# acl-adapter.net
KiCad netlist of a schematic drawn in EAGLE
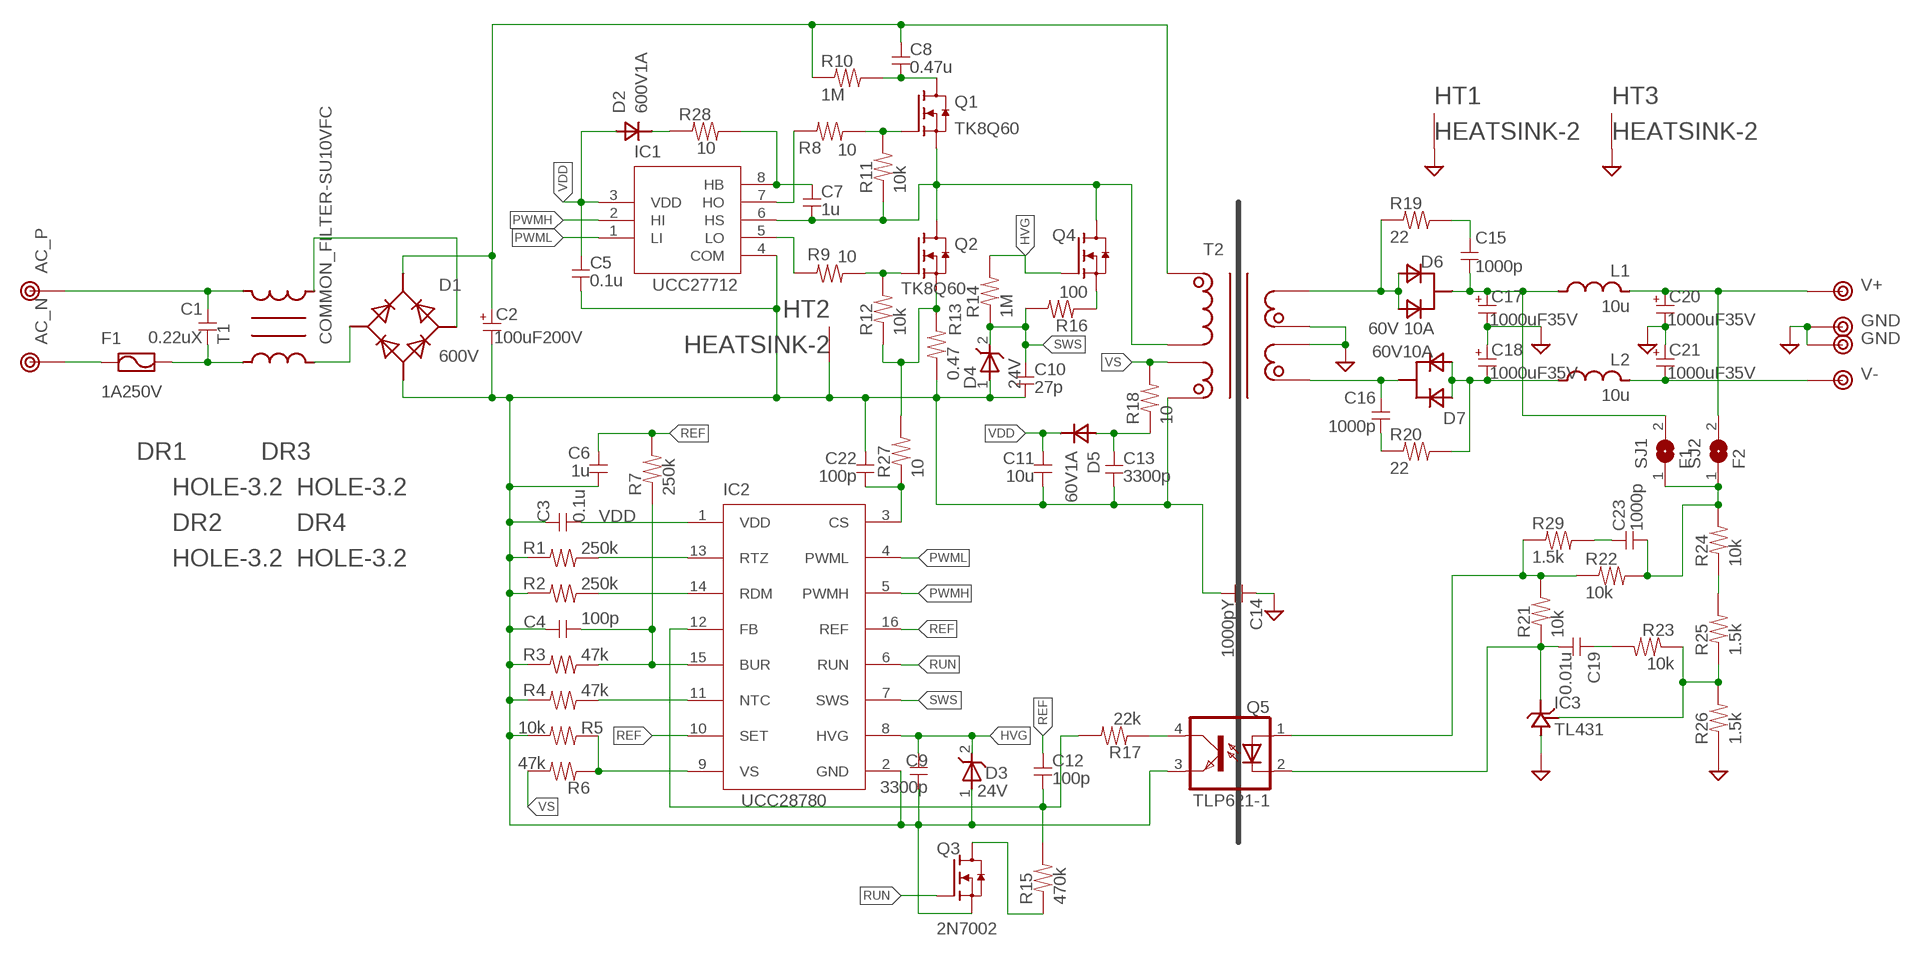
[diagram p0: schematic, sheet 1]

(export (version "E")
  (design (tool "Eeschema 10.0.6"))
  (components
    (comp (ref "C1")
      (value "0.22uX")
      (footprint "eagle-import:X-CAPACITER")
      (libsource (lib "eagle-import") (part "C-X"))
    )
    (comp (ref "C2")
      (value "100uF200V")
      (footprint "eagle-import:E5-10,5A2")
      (libsource (lib "eagle-import") (part "CPOLE5-10.5A2"))
    )
    (comp (ref "C3")
      (value "0.1u")
      (footprint "eagle-import:1608")
      (libsource (lib "eagle-import") (part "C-1608"))
    )
    (comp (ref "C4")
      (value "100p")
      (footprint "eagle-import:1608")
      (libsource (lib "eagle-import") (part "C-1608"))
    )
    (comp (ref "C5")
      (value "0.1u")
      (footprint "eagle-import:1608")
      (libsource (lib "eagle-import") (part "C-1608"))
    )
    (comp (ref "C6")
      (value "1u")
      (footprint "eagle-import:1608")
      (libsource (lib "eagle-import") (part "C-1608"))
    )
    (comp (ref "C7")
      (value "1u")
      (footprint "eagle-import:1608")
      (libsource (lib "eagle-import") (part "C-1608"))
    )
    (comp (ref "C8")
      (value "0.47u")
      (footprint "eagle-import:C075")
      (libsource (lib "eagle-import") (part "C-7.5"))
    )
    (comp (ref "C9")
      (value "3300p")
      (footprint "eagle-import:1608")
      (libsource (lib "eagle-import") (part "C-1608"))
    )
    (comp (ref "C10")
      (value "27p")
      (footprint "eagle-import:1608")
      (libsource (lib "eagle-import") (part "C-1608"))
    )
    (comp (ref "C11")
      (value "10u")
      (footprint "eagle-import:2012")
      (libsource (lib "eagle-import") (part "C-2012"))
    )
    (comp (ref "C12")
      (value "100p")
      (footprint "eagle-import:1608")
      (libsource (lib "eagle-import") (part "C-1608"))
    )
    (comp (ref "C13")
      (value "3300p")
      (footprint "eagle-import:1608")
      (libsource (lib "eagle-import") (part "C-1608"))
    )
    (comp (ref "C14")
      (value "1000pY")
      (footprint "eagle-import:Y-CAPACITER")
      (libsource (lib "eagle-import") (part "C-Y"))
    )
    (comp (ref "C15")
      (value "1000p")
      (footprint "eagle-import:1608")
      (libsource (lib "eagle-import") (part "C-1608"))
    )
    (comp (ref "C16")
      (value "1000p")
      (footprint "eagle-import:1608")
      (libsource (lib "eagle-import") (part "C-1608"))
    )
    (comp (ref "C17")
      (value "1000uF35V")
      (footprint "eagle-import:E5-10")
      (libsource (lib "eagle-import") (part "CPOLE5-10"))
    )
    (comp (ref "C18")
      (value "1000uF35V")
      (footprint "eagle-import:E5-10")
      (libsource (lib "eagle-import") (part "CPOLE5-10"))
    )
    (comp (ref "C19")
      (value "0.01u")
      (footprint "eagle-import:1608")
      (libsource (lib "eagle-import") (part "C-1608"))
    )
    (comp (ref "C20")
      (value "1000uF35V")
      (footprint "eagle-import:E5-10")
      (libsource (lib "eagle-import") (part "CPOLE5-10"))
    )
    (comp (ref "C21")
      (value "1000uF35V")
      (footprint "eagle-import:E5-10")
      (libsource (lib "eagle-import") (part "CPOLE5-10"))
    )
    (comp (ref "C22")
      (value "100p")
      (footprint "eagle-import:1608")
      (libsource (lib "eagle-import") (part "C-1608"))
    )
    (comp (ref "C23")
      (value "1000p")
      (footprint "eagle-import:1608")
      (libsource (lib "eagle-import") (part "C-1608"))
    )
    (comp (ref "D1")
      (value "600V")
      (footprint "eagle-import:GBU8A")
      (libsource (lib "eagle-import") (part "DIODE4-GBU8A"))
    )
    (comp (ref "D2")
      (value "600V1A")
      (footprint "eagle-import:D0204_7")
      (libsource (lib "eagle-import") (part "DIODE-7"))
    )
    (comp (ref "D3")
      (value "24V")
      (footprint "eagle-import:SOD123")
      (libsource (lib "eagle-import") (part "ZENER-SMD"))
    )
    (comp (ref "D4")
      (value "24V")
      (footprint "eagle-import:SOD123")
      (libsource (lib "eagle-import") (part "ZENER-SMD"))
    )
    (comp (ref "D5")
      (value "60V1A")
      (footprint "eagle-import:D0204_7")
      (libsource (lib "eagle-import") (part "DIODE-7"))
    )
    (comp (ref "D6")
      (value "60V 10A")
      (footprint "eagle-import:TO-220")
      (libsource (lib "eagle-import") (part "DIODE2"))
    )
    (comp (ref "D7")
      (value "60V10A")
      (footprint "eagle-import:TO-220")
      (libsource (lib "eagle-import") (part "DIODE2"))
    )
    (comp (ref "DR1")
      (value "HOLE-3.2")
      (footprint "eagle-import:HOLE_3.2")
      (libsource (lib "eagle-import") (part "HOLE-3.2"))
    )
    (comp (ref "DR2")
      (value "HOLE-3.2")
      (footprint "eagle-import:HOLE_3.2")
      (libsource (lib "eagle-import") (part "HOLE-3.2"))
    )
    (comp (ref "DR3")
      (value "HOLE-3.2")
      (footprint "eagle-import:HOLE_3.2")
      (libsource (lib "eagle-import") (part "HOLE-3.2"))
    )
    (comp (ref "DR4")
      (value "HOLE-3.2")
      (footprint "eagle-import:HOLE_3.2")
      (libsource (lib "eagle-import") (part "HOLE-3.2"))
    )
    (comp (ref "F1")
      (value "1A250V")
      (footprint "eagle-import:FUSE-5")
      (libsource (lib "eagle-import") (part "FUSE-5"))
    )
    (comp (ref "HT1")
      (value "HEATSINK-2")
      (footprint "eagle-import:HEATSINK2")
      (libsource (lib "eagle-import") (part "HEATSINK-2"))
    )
    (comp (ref "HT2")
      (value "HEATSINK-2")
      (footprint "eagle-import:HEATSINK2")
      (libsource (lib "eagle-import") (part "HEATSINK-2"))
    )
    (comp (ref "HT3")
      (value "HEATSINK-2")
      (footprint "eagle-import:HEATSINK2")
      (libsource (lib "eagle-import") (part "HEATSINK-2"))
    )
    (comp (ref "IC1")
      (value "UCC27712")
      (footprint "eagle-import:SOP8")
      (libsource (lib "eagle-import") (part "UCC27712"))
    )
    (comp (ref "IC2")
      (value "UCC28780")
      (footprint "eagle-import:SO16")
      (libsource (lib "eagle-import") (part "UCC28780"))
    )
    (comp (ref "IC3")
      (value "TL431")
      (footprint "eagle-import:TO-92")
      (libsource (lib "eagle-import") (part "TL431"))
    )
    (comp (ref "L1")
      (value "10u")
      (footprint "eagle-import:L5-7,5")
      (libsource (lib "eagle-import") (part "L-5"))
    )
    (comp (ref "L2")
      (value "10u")
      (footprint "eagle-import:L5-7,5")
      (libsource (lib "eagle-import") (part "L-5"))
    )
    (comp (ref "Q1")
      (value "TK8Q60")
      (footprint "eagle-import:TO-220")
      (libsource (lib "eagle-import") (part "NMOS"))
    )
    (comp (ref "Q2")
      (value "TK8Q60")
      (footprint "eagle-import:TO-220")
      (libsource (lib "eagle-import") (part "NMOS"))
    )
    (comp (ref "Q3")
      (value "2N7002")
      (footprint "eagle-import:SC59")
      (libsource (lib "eagle-import") (part "NMOS-SMD"))
    )
    (comp (ref "Q4")
      (value "NMOS-SMD")
      (footprint "eagle-import:SC59")
      (libsource (lib "eagle-import") (part "NMOS-SMD"))
    )
    (comp (ref "Q5")
      (value "TLP621-1")
      (footprint "eagle-import:DIL04")
      (libsource (lib "eagle-import") (part "TLP621-1"))
    )
    (comp (ref "R1")
      (value "250k")
      (footprint "eagle-import:1608")
      (libsource (lib "eagle-import") (part "R-1608"))
    )
    (comp (ref "R2")
      (value "250k")
      (footprint "eagle-import:1608")
      (libsource (lib "eagle-import") (part "R-1608"))
    )
    (comp (ref "R3")
      (value "47k")
      (footprint "eagle-import:1608")
      (libsource (lib "eagle-import") (part "R-1608"))
    )
    (comp (ref "R4")
      (value "47k")
      (footprint "eagle-import:1608")
      (libsource (lib "eagle-import") (part "R-1608"))
    )
    (comp (ref "R5")
      (value "10k")
      (footprint "eagle-import:1608")
      (libsource (lib "eagle-import") (part "R-1608"))
    )
    (comp (ref "R6")
      (value "47k")
      (footprint "eagle-import:1608")
      (libsource (lib "eagle-import") (part "R-1608"))
    )
    (comp (ref "R7")
      (value "250k")
      (footprint "eagle-import:1608")
      (libsource (lib "eagle-import") (part "R-1608"))
    )
    (comp (ref "R8")
      (value "10")
      (footprint "eagle-import:1608")
      (libsource (lib "eagle-import") (part "R-1608"))
    )
    (comp (ref "R9")
      (value "10")
      (footprint "eagle-import:1608")
      (libsource (lib "eagle-import") (part "R-1608"))
    )
    (comp (ref "R10")
      (value "1M")
      (footprint "eagle-import:0204_7")
      (libsource (lib "eagle-import") (part "R-7.5"))
    )
    (comp (ref "R11")
      (value "10k")
      (footprint "eagle-import:1608")
      (libsource (lib "eagle-import") (part "R-1608"))
    )
    (comp (ref "R12")
      (value "10k")
      (footprint "eagle-import:1608")
      (libsource (lib "eagle-import") (part "R-1608"))
    )
    (comp (ref "R13")
      (value "0.47")
      (footprint "eagle-import:0207_10")
      (libsource (lib "eagle-import") (part "R-10"))
    )
    (comp (ref "R14")
      (value "1M")
      (footprint "eagle-import:1608")
      (libsource (lib "eagle-import") (part "R-1608"))
    )
    (comp (ref "R15")
      (value "470k")
      (footprint "eagle-import:1608")
      (libsource (lib "eagle-import") (part "R-1608"))
    )
    (comp (ref "R16")
      (value "100")
      (footprint "eagle-import:1608")
      (libsource (lib "eagle-import") (part "R-1608"))
    )
    (comp (ref "R17")
      (value "22k")
      (footprint "eagle-import:1608")
      (libsource (lib "eagle-import") (part "R-1608"))
    )
    (comp (ref "R18")
      (value "10")
      (footprint "eagle-import:1608")
      (libsource (lib "eagle-import") (part "R-1608"))
    )
    (comp (ref "R19")
      (value "22")
      (footprint "eagle-import:0207_2V")
      (libsource (lib "eagle-import") (part "R-2.5"))
    )
    (comp (ref "R20")
      (value "22")
      (footprint "eagle-import:0207_2V")
      (libsource (lib "eagle-import") (part "R-2.5"))
    )
    (comp (ref "R21")
      (value "10k")
      (footprint "eagle-import:1608")
      (libsource (lib "eagle-import") (part "R-1608"))
    )
    (comp (ref "R22")
      (value "10k")
      (footprint "eagle-import:1608")
      (libsource (lib "eagle-import") (part "R-1608"))
    )
    (comp (ref "R23")
      (value "10k")
      (footprint "eagle-import:1608")
      (libsource (lib "eagle-import") (part "R-1608"))
    )
    (comp (ref "R24")
      (value "10k")
      (footprint "eagle-import:1608")
      (libsource (lib "eagle-import") (part "R-1608"))
    )
    (comp (ref "R25")
      (value "1.5k")
      (footprint "eagle-import:1608")
      (libsource (lib "eagle-import") (part "R-1608"))
    )
    (comp (ref "R26")
      (value "1.5k")
      (footprint "eagle-import:1608")
      (libsource (lib "eagle-import") (part "R-1608"))
    )
    (comp (ref "R27")
      (value "10")
      (footprint "eagle-import:1608")
      (libsource (lib "eagle-import") (part "R-1608"))
    )
    (comp (ref "R28")
      (value "10")
      (footprint "eagle-import:1608")
      (libsource (lib "eagle-import") (part "R-1608"))
    )
    (comp (ref "R29")
      (value "1.5k")
      (footprint "eagle-import:1608")
      (libsource (lib "eagle-import") (part "R-1608"))
    )
    (comp (ref "SJ1")
      (value "F1")
      (footprint "eagle-import:SJ1608")
      (libsource (lib "eagle-import") (part "SJ1608"))
    )
    (comp (ref "SJ2")
      (value "F2")
      (footprint "eagle-import:SJ1608")
      (libsource (lib "eagle-import") (part "SJ1608"))
    )
    (comp (ref "T1")
      (value "COMMON_FILTER-SU10VFC")
      (footprint "eagle-import:SU10VFC")
      (libsource (lib "eagle-import") (part "COMMON_FILTER-SU10VFC"))
    )
    (comp (ref "T2")
      (value "TRANSFORMAER_FLYBACK-PQ2620-ACF")
      (footprint "eagle-import:BPQ26_20-1112CPFR")
      (libsource (lib "eagle-import") (part "TRANSFORMAER_FLYBACK-PQ2620-ACF"))
    )
    (comp (ref "TP1")
      (value "AC_P")
      (footprint "eagle-import:TESTPIN-BIG")
      (libsource (lib "eagle-import") (part "TESTPIN-BIG"))
    )
    (comp (ref "TP2")
      (value "AC_N")
      (footprint "eagle-import:TESTPIN-BIG")
      (libsource (lib "eagle-import") (part "TESTPIN-BIG"))
    )
    (comp (ref "TP3")
      (value "V+")
      (footprint "eagle-import:TESTPIN-BIG")
      (libsource (lib "eagle-import") (part "TESTPIN-BIG"))
    )
    (comp (ref "TP4")
      (value "GND")
      (footprint "eagle-import:TESTPIN-BIG")
      (libsource (lib "eagle-import") (part "TESTPIN-BIG"))
    )
    (comp (ref "TP5")
      (value "V-")
      (footprint "eagle-import:TESTPIN-BIG")
      (libsource (lib "eagle-import") (part "TESTPIN-BIG"))
    )
    (comp (ref "TP6")
      (value "GND")
      (footprint "eagle-import:TESTPIN-BIG")
      (libsource (lib "eagle-import") (part "TESTPIN-BIG"))
    )
  )
  (nets
    (net (code "1") (name "GND") (class "Default")
      (node (ref "C14") (pin "1") (pinfunction "1_1") (pintype "passive"))
      (node (ref "C17") (pin "-") (pinfunction "2_-") (pintype "passive"))
      (node (ref "C18") (pin "+") (pinfunction "1_+") (pintype "passive"))
      (node (ref "C20") (pin "-") (pinfunction "2_-") (pintype "passive"))
      (node (ref "C21") (pin "+") (pinfunction "1_+") (pintype "passive"))
      (node (ref "HT1") (pin "HT1") (pinfunction "HT_HT1") (pintype "passive"))
      (node (ref "HT3") (pin "HT1") (pinfunction "HT_HT1") (pintype "passive"))
      (node (ref "IC3") (pin "2") (pinfunction "GND_2") (pintype "bidirectional"))
      (node (ref "R26") (pin "1") (pinfunction "1_1") (pintype "passive"))
      (node (ref "T2") (pin "10") (pinfunction "L4_N_10") (pintype "passive"))
      (node (ref "T2") (pin "9") (pinfunction "L3_P_9") (pintype "passive"))
      (node (ref "TP4") (pin "1") (pinfunction "1_1") (pintype "passive"))
      (node (ref "TP6") (pin "1") (pinfunction "1_1") (pintype "passive"))
    )
    (net (code "2") (name "HVG") (class "Default")
      (node (ref "C9") (pin "1") (pinfunction "1_1") (pintype "passive"))
      (node (ref "D3") (pin "2") (pinfunction "C_2") (pintype "bidirectional"))
      (node (ref "IC2") (pin "8") (pinfunction "HVG_8") (pintype "open_collector"))
      (node (ref "Q4") (pin "1") (pinfunction "G_1") (pintype "passive"))
      (node (ref "R14") (pin "2") (pinfunction "2_2") (pintype "passive"))
    )
    (net (code "3") (name "Net-(C1-Pad1)") (class "Default")
      (node (ref "C1") (pin "1") (pinfunction "1_1") (pintype "passive"))
      (node (ref "T1") (pin "4") (pinfunction "4_4") (pintype "passive"))
      (node (ref "TP1") (pin "1") (pinfunction "1_1") (pintype "passive"))
    )
    (net (code "4") (name "Net-(C2-1)") (class "Default")
      (node (ref "C2") (pin "+") (pinfunction "1_+") (pintype "passive"))
      (node (ref "C8") (pin "1") (pinfunction "1_1") (pintype "passive"))
      (node (ref "D1") (pin "1") (pinfunction "V+_1") (pintype "passive"))
      (node (ref "R10") (pin "1") (pinfunction "1_1") (pintype "passive"))
      (node (ref "T2") (pin "3") (pinfunction "L1_P_3") (pintype "passive"))
    )
    (net (code "5") (name "Net-(C2-2)") (class "Default")
      (node (ref "C10") (pin "2") (pinfunction "2_2") (pintype "passive"))
      (node (ref "C11") (pin "2") (pinfunction "2_2") (pintype "passive"))
      (node (ref "C13") (pin "2") (pinfunction "2_2") (pintype "passive"))
      (node (ref "C14") (pin "2") (pinfunction "2_2") (pintype "passive"))
      (node (ref "C2") (pin "-") (pinfunction "2_-") (pintype "passive"))
      (node (ref "C22") (pin "1") (pinfunction "1_1") (pintype "passive"))
      (node (ref "C3") (pin "1") (pinfunction "1_1") (pintype "passive"))
      (node (ref "C4") (pin "1") (pinfunction "1_1") (pintype "passive"))
      (node (ref "C5") (pin "2") (pinfunction "2_2") (pintype "passive"))
      (node (ref "C6") (pin "1") (pinfunction "1_1") (pintype "passive"))
      (node (ref "C9") (pin "2") (pinfunction "2_2") (pintype "passive"))
      (node (ref "D1") (pin "4") (pinfunction "V-_4") (pintype "passive"))
      (node (ref "D3") (pin "1") (pinfunction "A_1") (pintype "bidirectional"))
      (node (ref "D4") (pin "1") (pinfunction "A_1") (pintype "bidirectional"))
      (node (ref "HT2") (pin "HT1") (pinfunction "HT_HT1") (pintype "passive"))
      (node (ref "IC1") (pin "4") (pinfunction "COM_4") (pintype "power_in"))
      (node (ref "IC2") (pin "2") (pinfunction "GND_2") (pintype "power_in"))
      (node (ref "Q3") (pin "2") (pinfunction "S_2") (pintype "passive"))
      (node (ref "Q5") (pin "3") (pinfunction "EMIT_3") (pintype "passive"))
      (node (ref "R1") (pin "2") (pinfunction "2_2") (pintype "passive"))
      (node (ref "R13") (pin "1") (pinfunction "1_1") (pintype "passive"))
      (node (ref "R2") (pin "2") (pinfunction "2_2") (pintype "passive"))
      (node (ref "R3") (pin "1") (pinfunction "1_1") (pintype "passive"))
      (node (ref "R4") (pin "2") (pinfunction "2_2") (pintype "passive"))
      (node (ref "R5") (pin "2") (pinfunction "2_2") (pintype "passive"))
      (node (ref "T2") (pin "5") (pinfunction "L2_P_5") (pintype "passive"))
    )
    (net (code "6") (name "Net-(C15-Pad1)") (class "Default")
      (node (ref "C15") (pin "1") (pinfunction "1_1") (pintype "passive"))
      (node (ref "R19") (pin "2") (pinfunction "2_2") (pintype "passive"))
    )
    (net (code "7") (name "Net-(C16-Pad2)") (class "Default")
      (node (ref "C16") (pin "2") (pinfunction "2_2") (pintype "passive"))
      (node (ref "R20") (pin "1") (pinfunction "1_1") (pintype "passive"))
    )
    (net (code "8") (name "Net-(C17-1)") (class "Default")
      (node (ref "C15") (pin "2") (pinfunction "2_2") (pintype "passive"))
      (node (ref "C17") (pin "+") (pinfunction "1_+") (pintype "passive"))
      (node (ref "D6") (pin "2") (pinfunction "K_2") (pintype "passive"))
      (node (ref "L1") (pin "2") (pinfunction "1_2") (pintype "passive"))
      (node (ref "SJ1") (pin "2") (pinfunction "2_2") (pintype "passive"))
    )
    (net (code "9") (name "Net-(C18-2)") (class "Default")
      (node (ref "C18") (pin "-") (pinfunction "2_-") (pintype "passive"))
      (node (ref "D7") (pin "1") (pinfunction "A1_1") (pintype "passive"))
      (node (ref "D7") (pin "3") (pinfunction "A2_3") (pintype "passive"))
      (node (ref "L2") (pin "2") (pinfunction "1_2") (pintype "passive"))
      (node (ref "R20") (pin "2") (pinfunction "2_2") (pintype "passive"))
    )
    (net (code "10") (name "Net-(C19-Pad1)") (class "Default")
      (node (ref "C19") (pin "1") (pinfunction "1_1") (pintype "passive"))
      (node (ref "R23") (pin "2") (pinfunction "2_2") (pintype "passive"))
    )
    (net (code "11") (name "Net-(C20-1)") (class "Default")
      (node (ref "C20") (pin "+") (pinfunction "1_+") (pintype "passive"))
      (node (ref "L1") (pin "1") (pinfunction "2_1") (pintype "passive"))
      (node (ref "SJ2") (pin "2") (pinfunction "2_2") (pintype "passive"))
      (node (ref "TP3") (pin "1") (pinfunction "1_1") (pintype "passive"))
    )
    (net (code "12") (name "Net-(C21-2)") (class "Default")
      (node (ref "C21") (pin "-") (pinfunction "2_-") (pintype "passive"))
      (node (ref "L2") (pin "1") (pinfunction "2_1") (pintype "passive"))
      (node (ref "TP5") (pin "1") (pinfunction "1_1") (pintype "passive"))
    )
    (net (code "13") (name "Net-(C23-Pad1)") (class "Default")
      (node (ref "C23") (pin "1") (pinfunction "1_1") (pintype "passive"))
      (node (ref "R29") (pin "2") (pinfunction "2_2") (pintype "passive"))
    )
    (net (code "14") (name "Net-(C23-Pad2)") (class "Default")
      (node (ref "C23") (pin "2") (pinfunction "2_2") (pintype "passive"))
      (node (ref "R22") (pin "2") (pinfunction "2_2") (pintype "passive"))
      (node (ref "R24") (pin "2") (pinfunction "2_2") (pintype "passive"))
      (node (ref "SJ1") (pin "1") (pinfunction "1_1") (pintype "passive"))
      (node (ref "SJ2") (pin "1") (pinfunction "1_1") (pintype "passive"))
    )
    (net (code "15") (name "Net-(D1-AC1)") (class "Default")
      (node (ref "D1") (pin "2") (pinfunction "AC1_2") (pintype "passive"))
      (node (ref "T1") (pin "2") (pinfunction "2_2") (pintype "passive"))
    )
    (net (code "16") (name "Net-(D1-AC2)") (class "Default")
      (node (ref "D1") (pin "3") (pinfunction "AC2_3") (pintype "passive"))
      (node (ref "T1") (pin "3") (pinfunction "3_3") (pintype "passive"))
    )
    (net (code "17") (name "Net-(D2-K)") (class "Default")
      (node (ref "D2") (pin "2") (pinfunction "K_2") (pintype "passive"))
      (node (ref "R28") (pin "1") (pinfunction "1_1") (pintype "passive"))
    )
    (net (code "18") (name "Net-(D5-A)") (class "Default")
      (node (ref "C13") (pin "1") (pinfunction "1_1") (pintype "passive"))
      (node (ref "D5") (pin "1") (pinfunction "A_1") (pintype "passive"))
      (node (ref "R18") (pin "1") (pinfunction "1_1") (pintype "passive"))
    )
    (net (code "19") (name "Net-(D6-A1)") (class "Default")
      (node (ref "D6") (pin "1") (pinfunction "A1_1") (pintype "passive"))
      (node (ref "D6") (pin "3") (pinfunction "A2_3") (pintype "passive"))
      (node (ref "R19") (pin "1") (pinfunction "1_1") (pintype "passive"))
      (node (ref "T2") (pin "7") (pinfunction "L3_N_7") (pintype "passive"))
      (node (ref "T2") (pin "8") (pinfunction "L3_N_8") (pintype "passive"))
    )
    (net (code "20") (name "Net-(D7-K)") (class "Default")
      (node (ref "C16") (pin "1") (pinfunction "1_1") (pintype "passive"))
      (node (ref "D7") (pin "2") (pinfunction "K_2") (pintype "passive"))
      (node (ref "T2") (pin "11") (pinfunction "L4_P_11") (pintype "passive"))
      (node (ref "T2") (pin "12") (pinfunction "L4_P_12") (pintype "passive"))
    )
    (net (code "21") (name "Net-(F1-P$1)") (class "Default")
      (node (ref "F1") (pin "1") (pinfunction "P$1_1") (pintype "passive"))
      (node (ref "TP2") (pin "1") (pinfunction "1_1") (pintype "passive"))
    )
    (net (code "22") (name "Net-(F1-P$2)") (class "Default")
      (node (ref "C1") (pin "2") (pinfunction "2_2") (pintype "passive"))
      (node (ref "F1") (pin "2") (pinfunction "P$2_2") (pintype "passive"))
      (node (ref "T1") (pin "1") (pinfunction "1_1") (pintype "passive"))
    )
    (net (code "23") (name "Net-(IC1-HB)") (class "Default")
      (node (ref "C7") (pin "1") (pinfunction "1_1") (pintype "passive"))
      (node (ref "IC1") (pin "8") (pinfunction "HB_8") (pintype "power_in"))
      (node (ref "R28") (pin "2") (pinfunction "2_2") (pintype "passive"))
    )
    (net (code "24") (name "Net-(IC1-HO)") (class "Default")
      (node (ref "IC1") (pin "7") (pinfunction "HO_7") (pintype "output"))
      (node (ref "R8") (pin "2") (pinfunction "2_2") (pintype "passive"))
    )
    (net (code "25") (name "Net-(IC1-HS)") (class "Default")
      (node (ref "C7") (pin "2") (pinfunction "2_2") (pintype "passive"))
      (node (ref "IC1") (pin "6") (pinfunction "HS_6") (pintype "power_in"))
      (node (ref "Q1") (pin "3") (pinfunction "S_3") (pintype "passive"))
      (node (ref "Q2") (pin "2") (pinfunction "D_2") (pintype "passive"))
      (node (ref "Q4") (pin "3") (pinfunction "D_3") (pintype "passive"))
      (node (ref "R11") (pin "1") (pinfunction "1_1") (pintype "passive"))
      (node (ref "T2") (pin "1") (pinfunction "L1_N_1") (pintype "passive"))
    )
    (net (code "26") (name "Net-(IC1-LO)") (class "Default")
      (node (ref "IC1") (pin "5") (pinfunction "LO_5") (pintype "output"))
      (node (ref "R9") (pin "2") (pinfunction "2_2") (pintype "passive"))
    )
    (net (code "27") (name "Net-(IC2-BUR)") (class "Default")
      (node (ref "C4") (pin "2") (pinfunction "2_2") (pintype "passive"))
      (node (ref "IC2") (pin "15") (pinfunction "BUR_15") (pintype "input"))
      (node (ref "R3") (pin "2") (pinfunction "2_2") (pintype "passive"))
      (node (ref "R7") (pin "1") (pinfunction "1_1") (pintype "passive"))
    )
    (net (code "28") (name "Net-(IC2-CS)") (class "Default")
      (node (ref "C22") (pin "2") (pinfunction "2_2") (pintype "passive"))
      (node (ref "IC2") (pin "3") (pinfunction "CS_3") (pintype "input"))
      (node (ref "R27") (pin "1") (pinfunction "1_1") (pintype "passive"))
    )
    (net (code "29") (name "Net-(IC2-FB)") (class "Default")
      (node (ref "C12") (pin "2") (pinfunction "2_2") (pintype "passive"))
      (node (ref "IC2") (pin "12") (pinfunction "FB_12") (pintype "input"))
      (node (ref "R15") (pin "2") (pinfunction "2_2") (pintype "passive"))
      (node (ref "R17") (pin "2") (pinfunction "2_2") (pintype "passive"))
    )
    (net (code "30") (name "Net-(IC2-NTC)") (class "Default")
      (node (ref "IC2") (pin "11") (pinfunction "NTC_11") (pintype "passive"))
      (node (ref "R4") (pin "1") (pinfunction "1_1") (pintype "passive"))
    )
    (net (code "31") (name "Net-(IC2-RDM)") (class "Default")
      (node (ref "IC2") (pin "14") (pinfunction "RDM_14") (pintype "input"))
      (node (ref "R2") (pin "1") (pinfunction "1_1") (pintype "passive"))
    )
    (net (code "32") (name "Net-(IC2-RTZ)") (class "Default")
      (node (ref "IC2") (pin "13") (pinfunction "RTZ_13") (pintype "input"))
      (node (ref "R1") (pin "1") (pinfunction "1_1") (pintype "passive"))
    )
    (net (code "33") (name "Net-(IC2-VS)") (class "Default")
      (node (ref "IC2") (pin "9") (pinfunction "VS_9") (pintype "input"))
      (node (ref "R5") (pin "1") (pinfunction "1_1") (pintype "passive"))
      (node (ref "R6") (pin "1") (pinfunction "1_1") (pintype "passive"))
    )
    (net (code "34") (name "Net-(IC3-OUT)") (class "Default")
      (node (ref "C19") (pin "2") (pinfunction "2_2") (pintype "passive"))
      (node (ref "IC3") (pin "3") (pinfunction "OUT_3") (pintype "bidirectional"))
      (node (ref "Q5") (pin "2") (pinfunction "C_2") (pintype "passive"))
      (node (ref "R21") (pin "1") (pinfunction "1_1") (pintype "passive"))
    )
    (net (code "35") (name "Net-(IC3-REF)") (class "Default")
      (node (ref "IC3") (pin "1") (pinfunction "REF_1") (pintype "input"))
      (node (ref "R23") (pin "1") (pinfunction "1_1") (pintype "passive"))
      (node (ref "R25") (pin "1") (pinfunction "1_1") (pintype "passive"))
      (node (ref "R26") (pin "2") (pinfunction "2_2") (pintype "passive"))
    )
    (net (code "36") (name "Net-(Q1-D)") (class "Default")
      (node (ref "C8") (pin "2") (pinfunction "2_2") (pintype "passive"))
      (node (ref "Q1") (pin "2") (pinfunction "D_2") (pintype "passive"))
      (node (ref "R10") (pin "2") (pinfunction "2_2") (pintype "passive"))
    )
    (net (code "37") (name "Net-(Q1-G)") (class "Default")
      (node (ref "Q1") (pin "1") (pinfunction "G_1") (pintype "passive"))
      (node (ref "R11") (pin "2") (pinfunction "2_2") (pintype "passive"))
      (node (ref "R8") (pin "1") (pinfunction "1_1") (pintype "passive"))
    )
    (net (code "38") (name "Net-(Q2-G)") (class "Default")
      (node (ref "Q2") (pin "1") (pinfunction "G_1") (pintype "passive"))
      (node (ref "R12") (pin "2") (pinfunction "2_2") (pintype "passive"))
      (node (ref "R9") (pin "1") (pinfunction "1_1") (pintype "passive"))
    )
    (net (code "39") (name "Net-(Q2-S)") (class "Default")
      (node (ref "Q2") (pin "3") (pinfunction "S_3") (pintype "passive"))
      (node (ref "R12") (pin "1") (pinfunction "1_1") (pintype "passive"))
      (node (ref "R13") (pin "2") (pinfunction "2_2") (pintype "passive"))
      (node (ref "R27") (pin "2") (pinfunction "2_2") (pintype "passive"))
    )
    (net (code "40") (name "Net-(Q3-D)") (class "Default")
      (node (ref "Q3") (pin "3") (pinfunction "D_3") (pintype "passive"))
      (node (ref "R15") (pin "1") (pinfunction "1_1") (pintype "passive"))
    )
    (net (code "41") (name "Net-(Q4-S)") (class "Default")
      (node (ref "Q4") (pin "2") (pinfunction "S_2") (pintype "passive"))
      (node (ref "R16") (pin "1") (pinfunction "1_1") (pintype "passive"))
    )
    (net (code "42") (name "Net-(Q5-A)") (class "Default")
      (node (ref "Q5") (pin "1") (pinfunction "A_1") (pintype "passive"))
      (node (ref "R21") (pin "2") (pinfunction "2_2") (pintype "passive"))
      (node (ref "R22") (pin "1") (pinfunction "1_1") (pintype "passive"))
      (node (ref "R29") (pin "1") (pinfunction "1_1") (pintype "passive"))
    )
    (net (code "43") (name "Net-(Q5-COL)") (class "Default")
      (node (ref "Q5") (pin "4") (pinfunction "COL_4") (pintype "passive"))
      (node (ref "R17") (pin "1") (pinfunction "1_1") (pintype "passive"))
    )
    (net (code "44") (name "Net-(R24-Pad1)") (class "Default")
      (node (ref "R24") (pin "1") (pinfunction "1_1") (pintype "passive"))
      (node (ref "R25") (pin "2") (pinfunction "2_2") (pintype "passive"))
    )
    (net (code "45") (name "PWMH") (class "Default")
      (node (ref "IC1") (pin "2") (pinfunction "HI_2") (pintype "input"))
      (node (ref "IC2") (pin "5") (pinfunction "PWMH_5") (pintype "output"))
    )
    (net (code "46") (name "PWML") (class "Default")
      (node (ref "IC1") (pin "1") (pinfunction "LI_1") (pintype "input"))
      (node (ref "IC2") (pin "4") (pinfunction "PWML_4") (pintype "output"))
    )
    (net (code "47") (name "REF") (class "Default")
      (node (ref "C12") (pin "1") (pinfunction "1_1") (pintype "passive"))
      (node (ref "C6") (pin "2") (pinfunction "2_2") (pintype "passive"))
      (node (ref "IC2") (pin "10") (pinfunction "SET_10") (pintype "input"))
      (node (ref "IC2") (pin "16") (pinfunction "REF_16") (pintype "output"))
      (node (ref "R7") (pin "2") (pinfunction "2_2") (pintype "passive"))
    )
    (net (code "48") (name "RUN") (class "Default")
      (node (ref "IC2") (pin "6") (pinfunction "RUN_6") (pintype "output"))
      (node (ref "Q3") (pin "1") (pinfunction "G_1") (pintype "passive"))
    )
    (net (code "49") (name "SWS") (class "Default")
      (node (ref "C10") (pin "1") (pinfunction "1_1") (pintype "passive"))
      (node (ref "D4") (pin "2") (pinfunction "C_2") (pintype "bidirectional"))
      (node (ref "IC2") (pin "7") (pinfunction "SWS_7") (pintype "input"))
      (node (ref "R14") (pin "1") (pinfunction "1_1") (pintype "passive"))
      (node (ref "R16") (pin "2") (pinfunction "2_2") (pintype "passive"))
    )
    (net (code "50") (name "VDD") (class "Default")
      (node (ref "C11") (pin "1") (pinfunction "1_1") (pintype "passive"))
      (node (ref "C3") (pin "2") (pinfunction "2_2") (pintype "passive"))
      (node (ref "C5") (pin "1") (pinfunction "1_1") (pintype "passive"))
      (node (ref "D2") (pin "1") (pinfunction "A_1") (pintype "passive"))
      (node (ref "D5") (pin "2") (pinfunction "K_2") (pintype "passive"))
      (node (ref "IC1") (pin "3") (pinfunction "VDD_3") (pintype "power_in"))
      (node (ref "IC2") (pin "1") (pinfunction "VDD_1") (pintype "power_in"))
    )
    (net (code "51") (name "VS") (class "Default")
      (node (ref "R18") (pin "2") (pinfunction "2_2") (pintype "passive"))
      (node (ref "R6") (pin "2") (pinfunction "2_2") (pintype "passive"))
      (node (ref "T2") (pin "6") (pinfunction "L2_N_6") (pintype "passive"))
    )
  )
)
